# H1AR0.net
KiCad netlist of a schematic drawn in EAGLE
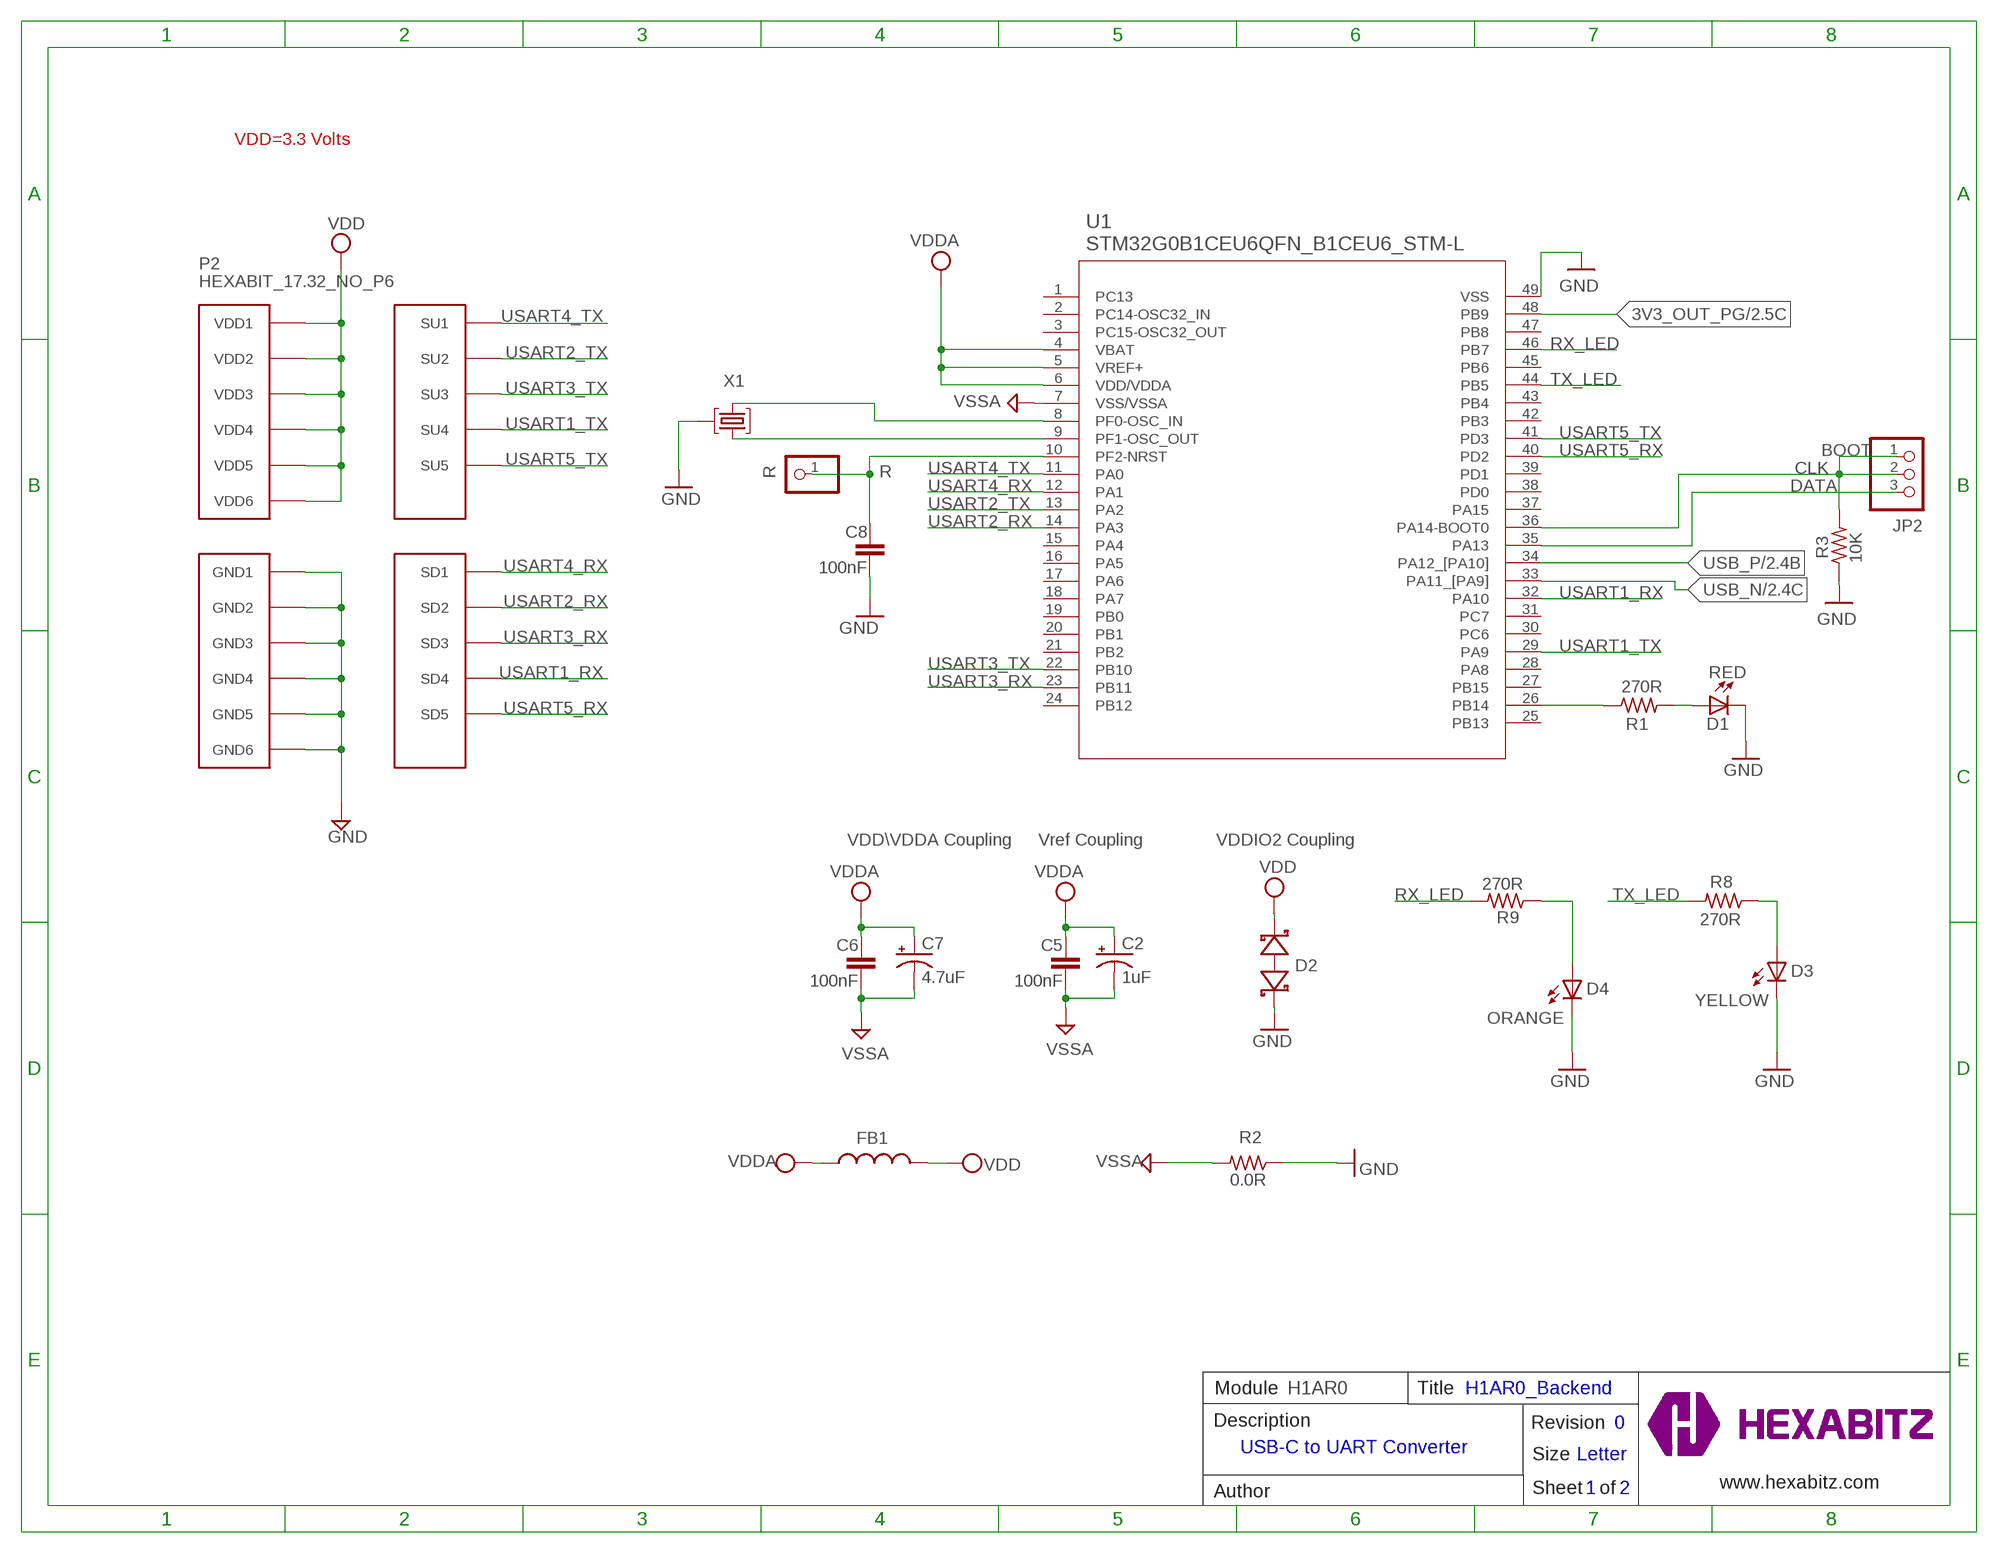
[diagram p0: schematic, sheet 1]
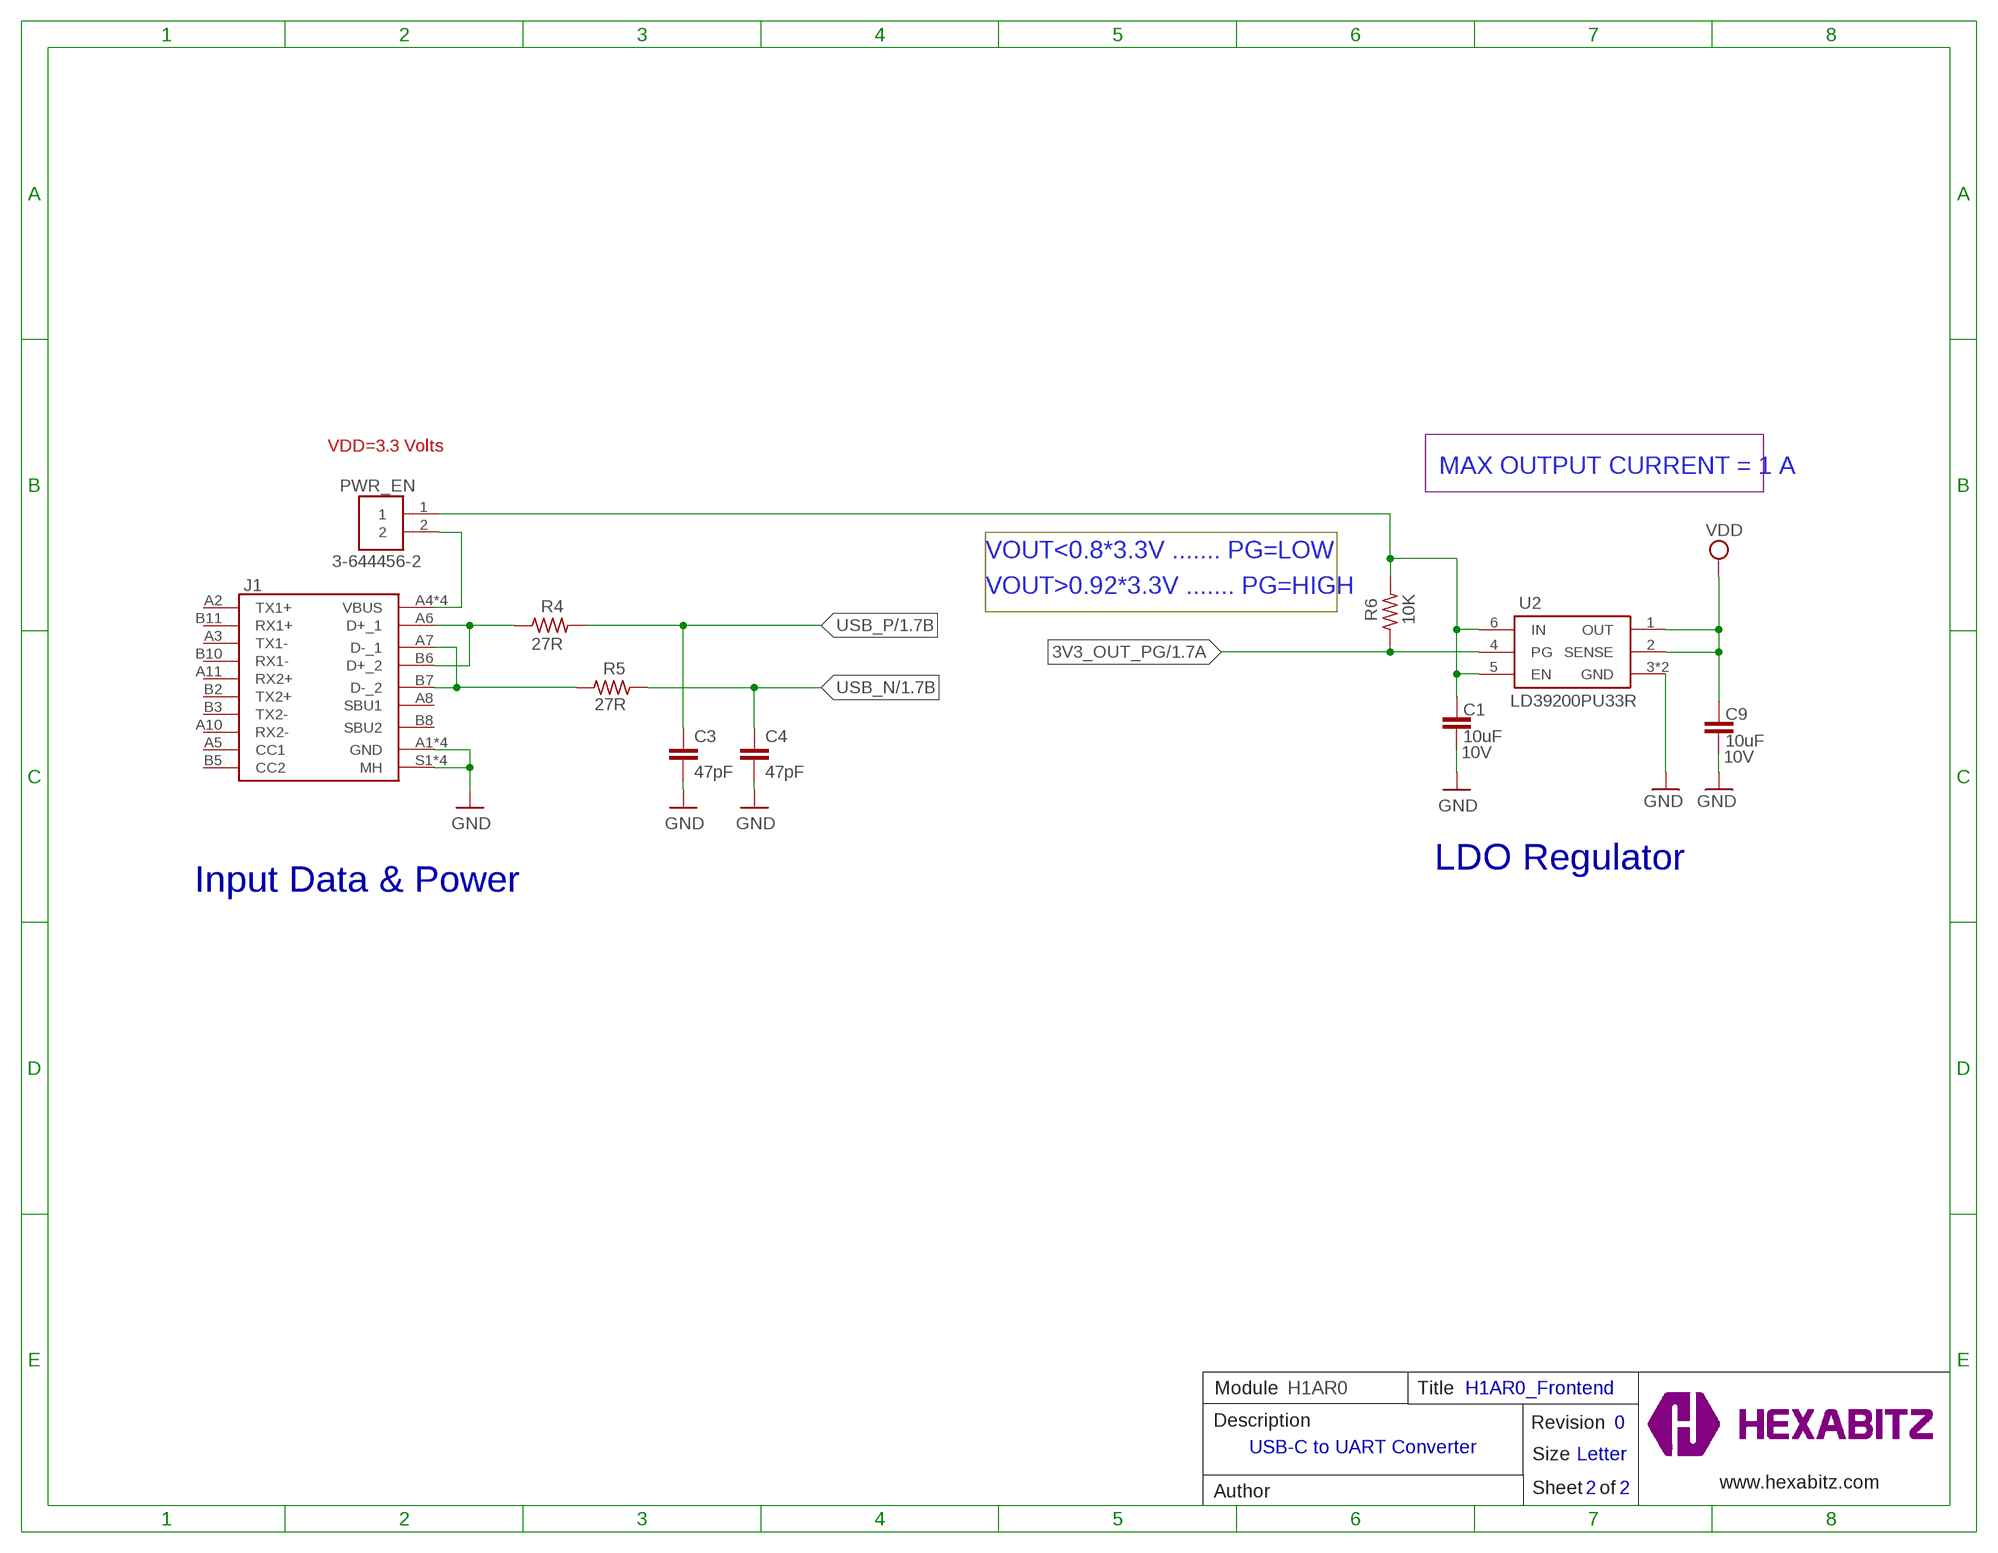
[diagram p1: schematic, sheet 2]

(export (version "E")
  (design (tool "Eeschema 10.0.6"))
  (components
    (comp (ref "C1")
      (value "10uF")
      (footprint "eagle-import:C-0805")
      (fields (field (name "MPN") "GRM187R61A226ME15") (field (name "VOLTAGE_RATING") "10V"))
      (libsource (lib "eagle-import") (part "C-0805"))
    )
    (comp (ref "C3")
      (value "47pF")
      (footprint "eagle-import:C-0603")
      (libsource (lib "eagle-import") (part "C-0603"))
    )
    (comp (ref "C4")
      (value "47pF")
      (footprint "eagle-import:C-0603")
      (libsource (lib "eagle-import") (part "C-0603"))
    )
    (comp (ref "C9")
      (value "10uF")
      (footprint "eagle-import:C-0805")
      (fields (field (name "MPN") "GRM187R61A226ME15") (field (name "VOLTAGE_RATING") "10V"))
      (libsource (lib "eagle-import") (part "C-0805"))
    )
    (comp (ref "J1")
      (value "12401610E4#2A12401610E42A")
      (footprint "eagle-import:AMPHENOL_12401610E4_2A")
      (libsource (lib "eagle-import") (part "12401610E4#2A12401610E42A"))
    )
    (comp (ref "PWR_EN")
      (value "3-644456-2")
      (footprint "eagle-import:TE_3-644456-2")
      (fields (field (name "MF") "TE Connectivity") (field (name "MPN") "87224-1"))
      (libsource (lib "eagle-import") (part "3-644456-2"))
    )
    (comp (ref "R4")
      (value "27R")
      (footprint "eagle-import:R-0603")
      (fields (field (name "TOLERANCE") "1%"))
      (libsource (lib "eagle-import") (part "R-0603"))
    )
    (comp (ref "R5")
      (value "27R")
      (footprint "eagle-import:R-0603")
      (fields (field (name "TOLERANCE") "1%"))
      (libsource (lib "eagle-import") (part "R-0603"))
    )
    (comp (ref "R6")
      (value "10K")
      (footprint "eagle-import:R-0603")
      (fields (field (name "TOLERANCE") "1%"))
      (libsource (lib "eagle-import") (part "R-0603"))
    )
    (comp (ref "U2")
      (value "LD39200PU33R")
      (footprint "eagle-import:SON95P300X300X100-7N")
      (fields (field (name "MOUSER_PART_NUMBER") "511-LD39200PU33R"))
      (libsource (lib "eagle-import") (part "LD39200PU33R"))
    )
    (comp (ref "C2")
      (value "1uF")
      (footprint "eagle-import:C-0805-POL")
      (libsource (lib "eagle-import") (part "C-0805-POL"))
    )
    (comp (ref "C5")
      (value "100nF")
      (footprint "eagle-import:C-0603")
      (libsource (lib "eagle-import") (part "C-0603"))
    )
    (comp (ref "C6")
      (value "100nF")
      (footprint "eagle-import:C-0603")
      (libsource (lib "eagle-import") (part "C-0603"))
    )
    (comp (ref "C7")
      (value "4.7uF")
      (footprint "eagle-import:C-0805-POL")
      (libsource (lib "eagle-import") (part "C-0805-POL"))
    )
    (comp (ref "C8")
      (value "100nF")
      (footprint "eagle-import:C-0603")
      (libsource (lib "eagle-import") (part "C-0603"))
    )
    (comp (ref "D1")
      (value "RED")
      (footprint "eagle-import:VLMS1300-GS08")
      (fields
        (field (name "MPN") "VLMS1300-GS08")
        (field (name "MFN") "Vishay")
        (field (name "MPN_1") "VLMS1300-GS08")
        (field (name "OCTOPART_URL") "https://octopart.com/vlms1300-gs08-vishay-21709201?r=sp&s=_gcP4_q8T1SC6PJQPTQ9yA")
      )
      (libsource (lib "eagle-import") (part "Hexabitz_VLMS1300-GS08"))
    )
    (comp (ref "D2")
      (value "BOURNS_CDSOD323-T03SCBOURNS_CDSOD323-T03SC_0_0")
      (footprint "eagle-import:BOURNS_CDSOD323-T03SC_0")
      (fields (field (name "MPN") "CDSOD323-T03SC"))
      (libsource (lib "eagle-import") (part "BOURNS_CDSOD323-T03SCBOURNS_CDSOD323-T03SC_0_0"))
    )
    (comp (ref "D3")
      (value "YELLOW")
      (footprint "eagle-import:VLMS1300-GS08")
      (fields
        (field (name "MPN") "VLMS1300-GS08")
        (field (name "OCTOPART_URL") "https://octopart.com/vlms1300-gs08-vishay-21709201?r=sp&s=_gcP4_q8T1SC6PJQPTQ9yA")
      )
      (libsource (lib "eagle-import") (part "VLMS1300-GS08"))
    )
    (comp (ref "D4")
      (value "ORANGE")
      (footprint "eagle-import:VLMS1300-GS08")
      (fields
        (field (name "MPN") "VLMS1300-GS08")
        (field (name "OCTOPART_URL") "https://octopart.com/vlms1300-gs08-vishay-21709201?r=sp&s=_gcP4_q8T1SC6PJQPTQ9yA")
      )
      (libsource (lib "eagle-import") (part "VLMS1300-GS08"))
    )
    (comp (ref "FB1")
      (value "FB-TDK_MMZ1608Y300B")
      (footprint "eagle-import:FB-TDK_MMZ1608Y300B")
      (fields
        (field (name "MFN") "TDK ")
        (field (name "MPN") "MMZ1608Y300B")
        (field (name "OCTOPART_URL") "https://octopart.com/mmz1608y300b-tdk-368280?r=sp&s=cd9_2ZEqQ9q9UNBuQgHAiA")
      )
      (libsource (lib "eagle-import") (part "FB-TDK_MMZ1608Y300B"))
    )
    (comp (ref "JP2")
      (value "PINHD-1X3")
      (footprint "eagle-import:1X03")
      (libsource (lib "eagle-import") (part "PINHD-1X3"))
    )
    (comp (ref "P2")
      (value "HEXABIT_17.32_NO_P6")
      (footprint "eagle-import:HEXABIT_17.32_NO_P6")
      (libsource (lib "eagle-import") (part "HEXABIT_?_NO_P617.32"))
    )
    (comp (ref "R")
      (value "R")
      (footprint "eagle-import:1X01")
      (fields (field (name "MPN") "87227-1"))
      (libsource (lib "eagle-import") (part "PINHD-1X1"))
    )
    (comp (ref "R1")
      (value "270R")
      (footprint "eagle-import:R-0603")
      (libsource (lib "eagle-import") (part "R-0603"))
    )
    (comp (ref "R2")
      (value "0.0R")
      (footprint "eagle-import:R-0603")
      (fields
        (field (name "MFN") "Yageo")
        (field (name "MPN") "RC0603JR-070RL")
        (field (name "OCTOPART_URL") "https://octopart.com/rc0603jr-070rl-yageo-1241539?r=sp&s=X2NteqRjRNWrnx42Y0aliA")
        (field (name "RESISTANCE") "0.0 Ohm")
      )
      (libsource (lib "eagle-import") (part "R-0603"))
    )
    (comp (ref "R3")
      (value "10K")
      (footprint "eagle-import:R-0603")
      (libsource (lib "eagle-import") (part "R-0603"))
    )
    (comp (ref "R8")
      (value "270R")
      (footprint "eagle-import:R-0603")
      (libsource (lib "eagle-import") (part "R-0603"))
    )
    (comp (ref "R9")
      (value "270R")
      (footprint "eagle-import:R-0603")
      (libsource (lib "eagle-import") (part "R-0603"))
    )
    (comp (ref "TRIMBLE-LOGO1")
      (value "HEXA-LOGO")
      (footprint "eagle-import:HEXA-LOGO")
      (libsource (lib "eagle-import") (part "HEXA-LOGO"))
    )
    (comp (ref "U1")
      (value "STM32G0B1CEU6QFN_B1CEU6_STM-L")
      (footprint "eagle-import:QFN_B1CEU6_STM-L")
      (fields
        (field (name "MANUFACTURER_PART_NUMBER") "STM32G0B1CEU6")
        (field (name "COPYRIGHT") "Copyright (C) 2021 Ultra Librarian. All rights reserved.")
      )
      (libsource (lib "eagle-import") (part "STM32G0B1CEU6QFN_B1CEU6_STM-L"))
    )
    (comp (ref "X1")
      (value "XTALL_CSTCE8M00G52")
      (footprint "eagle-import:XTALL_CSTCE8M00G52")
      (fields (field (name "MPN") "CSTCE8M00G52Z-R0"))
      (libsource (lib "eagle-import") (part "XTALL_CSTCE8M00G52"))
    )
  )
  (nets
    (net (code "1") (name "3V3_OUT_PG") (class "Default")
      (node (ref "R6") (pin "1") (pinfunction "1_1") (pintype "passive"))
      (node (ref "U1") (pin "48") (pinfunction "PB9_48") (pintype "bidirectional"))
      (node (ref "U2") (pin "4") (pinfunction "PG_4") (pintype "bidirectional"))
    )
    (net (code "2") (name "CLK") (class "Default")
      (node (ref "JP2") (pin "1") (pinfunction "1_1") (pintype "passive"))
      (node (ref "JP2") (pin "2") (pinfunction "2_2") (pintype "passive"))
      (node (ref "R3") (pin "2") (pinfunction "2_2") (pintype "passive"))
      (node (ref "U1") (pin "36") (pinfunction "PA14-BOOT0_36") (pintype "bidirectional"))
    )
    (net (code "3") (name "DATA") (class "Default")
      (node (ref "JP2") (pin "3") (pinfunction "3_3") (pintype "passive"))
      (node (ref "U1") (pin "35") (pinfunction "PA13_35") (pintype "bidirectional"))
    )
    (net (code "4") (name "GND") (class "Default")
      (node (ref "C1") (pin "1") (pinfunction "1_1") (pintype "passive"))
      (node (ref "C3") (pin "2") (pinfunction "2_2") (pintype "passive"))
      (node (ref "C4") (pin "2") (pinfunction "2_2") (pintype "passive"))
      (node (ref "C8") (pin "2") (pinfunction "2_2") (pintype "passive"))
      (node (ref "C9") (pin "1") (pinfunction "1_1") (pintype "passive"))
      (node (ref "D1") (pin "C") (pinfunction "C_C") (pintype "passive"))
      (node (ref "D2") (pin "1") (pinfunction "A_1") (pintype "passive"))
      (node (ref "D3") (pin "C") (pinfunction "C_C") (pintype "passive"))
      (node (ref "D4") (pin "C") (pinfunction "C_C") (pintype "passive"))
      (node (ref "J1") (pin "A1") (pinfunction "GND_A1") (pintype "bidirectional"))
      (node (ref "J1") (pin "A12") (pinfunction "GND_A12") (pintype "bidirectional"))
      (node (ref "J1") (pin "B1") (pinfunction "GND_B1") (pintype "bidirectional"))
      (node (ref "J1") (pin "B12") (pinfunction "GND_B12") (pintype "bidirectional"))
      (node (ref "J1") (pin "S1") (pinfunction "MH_S1") (pintype "bidirectional"))
      (node (ref "J1") (pin "S2") (pinfunction "MH_S2") (pintype "bidirectional"))
      (node (ref "J1") (pin "S3") (pinfunction "MH_S3") (pintype "bidirectional"))
      (node (ref "J1") (pin "S4") (pinfunction "MH_S4") (pintype "bidirectional"))
      (node (ref "P2") (pin "PAD_PD10") (pinfunction "GND4_PAD_PD10") (pintype "power_in"))
      (node (ref "P2") (pin "PAD_PD11") (pinfunction "GND5_PAD_PD11") (pintype "power_in"))
      (node (ref "P2") (pin "PAD_PD12") (pinfunction "GND6_PAD_PD12") (pintype "power_in"))
      (node (ref "P2") (pin "PAD_PD7") (pinfunction "GND1_PAD_PD7") (pintype "power_in"))
      (node (ref "P2") (pin "PAD_PD8") (pinfunction "GND2_PAD_PD8") (pintype "power_in"))
      (node (ref "P2") (pin "PAD_PD9") (pinfunction "GND3_PAD_PD9") (pintype "power_in"))
      (node (ref "R2") (pin "1") (pinfunction "1_1") (pintype "passive"))
      (node (ref "R3") (pin "1") (pinfunction "1_1") (pintype "passive"))
      (node (ref "U1") (pin "49") (pinfunction "VSS_49") (pintype "passive"))
      (node (ref "U2") (pin "3") (pinfunction "GND_3") (pintype "bidirectional"))
      (node (ref "U2") (pin "7") (pinfunction "GND_7") (pintype "bidirectional"))
      (node (ref "X1") (pin "P$2") (pinfunction "2_P$2") (pintype "passive"))
    )
    (net (code "5") (name "Net-(D1-PadA)") (class "Default")
      (node (ref "D1") (pin "A") (pinfunction "A_A") (pintype "passive"))
      (node (ref "R1") (pin "2") (pinfunction "2_2") (pintype "passive"))
    )
    (net (code "6") (name "Net-(D3-PadA)") (class "Default")
      (node (ref "D3") (pin "A") (pinfunction "A_A") (pintype "passive"))
      (node (ref "R8") (pin "1") (pinfunction "1_1") (pintype "passive"))
    )
    (net (code "7") (name "Net-(D4-PadA)") (class "Default")
      (node (ref "D4") (pin "A") (pinfunction "A_A") (pintype "passive"))
      (node (ref "R9") (pin "1") (pinfunction "1_1") (pintype "passive"))
    )
    (net (code "8") (name "Net-(J1-D+_1)") (class "Default")
      (node (ref "J1") (pin "A6") (pinfunction "D+_1_A6") (pintype "bidirectional"))
      (node (ref "J1") (pin "B6") (pinfunction "D+_2_B6") (pintype "bidirectional"))
      (node (ref "R4") (pin "1") (pinfunction "1_1") (pintype "passive"))
    )
    (net (code "9") (name "Net-(J1-D-_1)") (class "Default")
      (node (ref "J1") (pin "A7") (pinfunction "D-_1_A7") (pintype "bidirectional"))
      (node (ref "J1") (pin "B7") (pinfunction "D-_2_B7") (pintype "bidirectional"))
      (node (ref "R5") (pin "2") (pinfunction "2_2") (pintype "passive"))
    )
    (net (code "10") (name "Net-(J1-VBUS-PadA4)") (class "Default")
      (node (ref "J1") (pin "A4") (pinfunction "VBUS_A4") (pintype "bidirectional"))
      (node (ref "J1") (pin "A9") (pinfunction "VBUS_A9") (pintype "bidirectional"))
      (node (ref "J1") (pin "B4") (pinfunction "VBUS_B4") (pintype "bidirectional"))
      (node (ref "J1") (pin "B9") (pinfunction "VBUS_B9") (pintype "bidirectional"))
      (node (ref "PWR_EN") (pin "2") (pinfunction "2_2") (pintype "passive"))
    )
    (net (code "11") (name "Net-(U1-PB14)") (class "Default")
      (node (ref "R1") (pin "1") (pinfunction "1_1") (pintype "passive"))
      (node (ref "U1") (pin "26") (pinfunction "PB14_26") (pintype "bidirectional"))
    )
    (net (code "12") (name "Net-(U1-PF0-OSC_IN)") (class "Default")
      (node (ref "U1") (pin "8") (pinfunction "PF0-OSC_IN_8") (pintype "bidirectional"))
      (node (ref "X1") (pin "P$3") (pinfunction "3_P$3") (pintype "passive"))
    )
    (net (code "13") (name "Net-(U1-PF1-OSC_OUT)") (class "Default")
      (node (ref "U1") (pin "9") (pinfunction "PF1-OSC_OUT_9") (pintype "output"))
      (node (ref "X1") (pin "P$1") (pinfunction "1_P$1") (pintype "passive"))
    )
    (net (code "14") (name "Net-(U1-PF2-NRST)") (class "Default")
      (node (ref "C8") (pin "1") (pinfunction "1_1") (pintype "passive"))
      (node (ref "R") (pin "1") (pinfunction "1_1") (pintype "passive"))
      (node (ref "U1") (pin "10") (pinfunction "PF2-NRST_10") (pintype "bidirectional"))
    )
    (net (code "15") (name "Net-(U2-EN)") (class "Default")
      (node (ref "C1") (pin "2") (pinfunction "2_2") (pintype "passive"))
      (node (ref "PWR_EN") (pin "1") (pinfunction "1_1") (pintype "passive"))
      (node (ref "R6") (pin "2") (pinfunction "2_2") (pintype "passive"))
      (node (ref "U2") (pin "5") (pinfunction "EN_5") (pintype "bidirectional"))
      (node (ref "U2") (pin "6") (pinfunction "IN_6") (pintype "bidirectional"))
    )
    (net (code "16") (name "RX_LED") (class "Default")
      (node (ref "R9") (pin "2") (pinfunction "2_2") (pintype "passive"))
      (node (ref "U1") (pin "46") (pinfunction "PB7_46") (pintype "bidirectional"))
    )
    (net (code "17") (name "TX_LED") (class "Default")
      (node (ref "R8") (pin "2") (pinfunction "2_2") (pintype "passive"))
      (node (ref "U1") (pin "44") (pinfunction "PB5_44") (pintype "bidirectional"))
    )
    (net (code "18") (name "USART1_RX") (class "Default")
      (node (ref "P2") (pin "PAD_PD4") (pinfunction "SD4_PAD_PD4") (pintype "bidirectional"))
      (node (ref "U1") (pin "32") (pinfunction "PA10_32") (pintype "bidirectional"))
    )
    (net (code "19") (name "USART1_TX") (class "Default")
      (node (ref "P2") (pin "PAD_PU4") (pinfunction "SU4_PAD_PU4") (pintype "bidirectional"))
      (node (ref "U1") (pin "29") (pinfunction "PA9_29") (pintype "bidirectional"))
    )
    (net (code "20") (name "USART2_RX") (class "Default")
      (node (ref "P2") (pin "PAD_PD2") (pinfunction "SD2_PAD_PD2") (pintype "bidirectional"))
      (node (ref "U1") (pin "14") (pinfunction "PA3_14") (pintype "bidirectional"))
    )
    (net (code "21") (name "USART2_TX") (class "Default")
      (node (ref "P2") (pin "PAD_PU2") (pinfunction "SU2_PAD_PU2") (pintype "bidirectional"))
      (node (ref "U1") (pin "13") (pinfunction "PA2_13") (pintype "bidirectional"))
    )
    (net (code "22") (name "USART3_RX") (class "Default")
      (node (ref "P2") (pin "PAD_PD3") (pinfunction "SD3_PAD_PD3") (pintype "bidirectional"))
      (node (ref "U1") (pin "23") (pinfunction "PB11_23") (pintype "bidirectional"))
    )
    (net (code "23") (name "USART3_TX") (class "Default")
      (node (ref "P2") (pin "PAD_PU3") (pinfunction "SU3_PAD_PU3") (pintype "bidirectional"))
      (node (ref "U1") (pin "22") (pinfunction "PB10_22") (pintype "bidirectional"))
    )
    (net (code "24") (name "USART4_RX") (class "Default")
      (node (ref "P2") (pin "PAD_PD1") (pinfunction "SD1_PAD_PD1") (pintype "bidirectional"))
      (node (ref "U1") (pin "12") (pinfunction "PA1_12") (pintype "bidirectional"))
    )
    (net (code "25") (name "USART4_TX") (class "Default")
      (node (ref "P2") (pin "PAD_PU1") (pinfunction "SU1_PAD_PU1") (pintype "bidirectional"))
      (node (ref "U1") (pin "11") (pinfunction "PA0_11") (pintype "bidirectional"))
    )
    (net (code "26") (name "USART5_RX") (class "Default")
      (node (ref "P2") (pin "PAD_PD5") (pinfunction "SD5_PAD_PD5") (pintype "bidirectional"))
      (node (ref "U1") (pin "40") (pinfunction "PD2_40") (pintype "bidirectional"))
    )
    (net (code "27") (name "USART5_TX") (class "Default")
      (node (ref "P2") (pin "PAD_PU5") (pinfunction "SU5_PAD_PU5") (pintype "bidirectional"))
      (node (ref "U1") (pin "41") (pinfunction "PD3_41") (pintype "bidirectional"))
    )
    (net (code "28") (name "USB_N") (class "Default")
      (node (ref "C4") (pin "1") (pinfunction "1_1") (pintype "passive"))
      (node (ref "R5") (pin "1") (pinfunction "1_1") (pintype "passive"))
      (node (ref "U1") (pin "33") (pinfunction "PA11_[PA9]_33") (pintype "bidirectional"))
    )
    (net (code "29") (name "USB_P") (class "Default")
      (node (ref "C3") (pin "1") (pinfunction "1_1") (pintype "passive"))
      (node (ref "R4") (pin "2") (pinfunction "2_2") (pintype "passive"))
      (node (ref "U1") (pin "34") (pinfunction "PA12_[PA10]_34") (pintype "bidirectional"))
    )
    (net (code "30") (name "VDD") (class "Default")
      (node (ref "C9") (pin "2") (pinfunction "2_2") (pintype "passive"))
      (node (ref "D2") (pin "2") (pinfunction "C_2") (pintype "passive"))
      (node (ref "FB1") (pin "2") (pinfunction "2_2") (pintype "passive"))
      (node (ref "P2") (pin "PAD_PU10") (pinfunction "VDD4_PAD_PU10") (pintype "power_in"))
      (node (ref "P2") (pin "PAD_PU11") (pinfunction "VDD5_PAD_PU11") (pintype "power_in"))
      (node (ref "P2") (pin "PAD_PU12") (pinfunction "VDD6_PAD_PU12") (pintype "power_in"))
      (node (ref "P2") (pin "PAD_PU7") (pinfunction "VDD1_PAD_PU7") (pintype "power_in"))
      (node (ref "P2") (pin "PAD_PU8") (pinfunction "VDD2_PAD_PU8") (pintype "power_in"))
      (node (ref "P2") (pin "PAD_PU9") (pinfunction "VDD3_PAD_PU9") (pintype "power_in"))
      (node (ref "U2") (pin "1") (pinfunction "OUT_1") (pintype "bidirectional"))
      (node (ref "U2") (pin "2") (pinfunction "SENSE_2") (pintype "bidirectional"))
    )
    (net (code "31") (name "VDDA") (class "Default")
      (node (ref "C2") (pin "1") (pinfunction "+_1") (pintype "passive"))
      (node (ref "C5") (pin "1") (pinfunction "1_1") (pintype "passive"))
      (node (ref "C6") (pin "1") (pinfunction "1_1") (pintype "passive"))
      (node (ref "C7") (pin "1") (pinfunction "+_1") (pintype "passive"))
      (node (ref "FB1") (pin "1") (pinfunction "1_1") (pintype "passive"))
      (node (ref "U1") (pin "4") (pinfunction "VBAT_4") (pintype "passive"))
      (node (ref "U1") (pin "5") (pinfunction "VREF+_5") (pintype "power_in"))
      (node (ref "U1") (pin "6") (pinfunction "VDD/VDDA_6") (pintype "power_in"))
    )
    (net (code "32") (name "VSSA") (class "Default")
      (node (ref "C2") (pin "2") (pinfunction "-_2") (pintype "passive"))
      (node (ref "C5") (pin "2") (pinfunction "2_2") (pintype "passive"))
      (node (ref "C6") (pin "2") (pinfunction "2_2") (pintype "passive"))
      (node (ref "C7") (pin "2") (pinfunction "-_2") (pintype "passive"))
      (node (ref "R2") (pin "2") (pinfunction "2_2") (pintype "passive"))
      (node (ref "U1") (pin "7") (pinfunction "VSS/VSSA_7") (pintype "passive"))
    )
    (net (code "33") (name "unconnected-(J1-CC1-PadA5)") (class "Default")
      (node (ref "J1") (pin "A5") (pinfunction "CC1_A5") (pintype "bidirectional"))
    )
    (net (code "34") (name "unconnected-(J1-CC2-PadB5)") (class "Default")
      (node (ref "J1") (pin "B5") (pinfunction "CC2_B5") (pintype "bidirectional"))
    )
    (net (code "35") (name "unconnected-(J1-RX1+-PadB11)") (class "Default")
      (node (ref "J1") (pin "B11") (pinfunction "RX1+_B11") (pintype "bidirectional"))
    )
    (net (code "36") (name "unconnected-(J1-RX1--PadB10)") (class "Default")
      (node (ref "J1") (pin "B10") (pinfunction "RX1-_B10") (pintype "bidirectional"))
    )
    (net (code "37") (name "unconnected-(J1-RX2+-PadA11)") (class "Default")
      (node (ref "J1") (pin "A11") (pinfunction "RX2+_A11") (pintype "bidirectional"))
    )
    (net (code "38") (name "unconnected-(J1-RX2--PadA10)") (class "Default")
      (node (ref "J1") (pin "A10") (pinfunction "RX2-_A10") (pintype "bidirectional"))
    )
    (net (code "39") (name "unconnected-(J1-SBU1-PadA8)") (class "Default")
      (node (ref "J1") (pin "A8") (pinfunction "SBU1_A8") (pintype "bidirectional"))
    )
    (net (code "40") (name "unconnected-(J1-SBU2-PadB8)") (class "Default")
      (node (ref "J1") (pin "B8") (pinfunction "SBU2_B8") (pintype "bidirectional"))
    )
    (net (code "41") (name "unconnected-(J1-TX1+-PadA2)") (class "Default")
      (node (ref "J1") (pin "A2") (pinfunction "TX1+_A2") (pintype "bidirectional"))
    )
    (net (code "42") (name "unconnected-(J1-TX1--PadA3)") (class "Default")
      (node (ref "J1") (pin "A3") (pinfunction "TX1-_A3") (pintype "bidirectional"))
    )
    (net (code "43") (name "unconnected-(J1-TX2+-PadB2)") (class "Default")
      (node (ref "J1") (pin "B2") (pinfunction "TX2+_B2") (pintype "bidirectional"))
    )
    (net (code "44") (name "unconnected-(J1-TX2--PadB3)") (class "Default")
      (node (ref "J1") (pin "B3") (pinfunction "TX2-_B3") (pintype "bidirectional"))
    )
    (net (code "45") (name "unconnected-(U1-PA4-Pad15)") (class "Default")
      (node (ref "U1") (pin "15") (pinfunction "PA4_15") (pintype "bidirectional"))
    )
    (net (code "46") (name "unconnected-(U1-PA5-Pad16)") (class "Default")
      (node (ref "U1") (pin "16") (pinfunction "PA5_16") (pintype "bidirectional"))
    )
    (net (code "47") (name "unconnected-(U1-PA6-Pad17)") (class "Default")
      (node (ref "U1") (pin "17") (pinfunction "PA6_17") (pintype "bidirectional"))
    )
    (net (code "48") (name "unconnected-(U1-PA7-Pad18)") (class "Default")
      (node (ref "U1") (pin "18") (pinfunction "PA7_18") (pintype "bidirectional"))
    )
    (net (code "49") (name "unconnected-(U1-PA8-Pad28)") (class "Default")
      (node (ref "U1") (pin "28") (pinfunction "PA8_28") (pintype "bidirectional"))
    )
    (net (code "50") (name "unconnected-(U1-PA15-Pad37)") (class "Default")
      (node (ref "U1") (pin "37") (pinfunction "PA15_37") (pintype "bidirectional"))
    )
    (net (code "51") (name "unconnected-(U1-PB0-Pad19)") (class "Default")
      (node (ref "U1") (pin "19") (pinfunction "PB0_19") (pintype "bidirectional"))
    )
    (net (code "52") (name "unconnected-(U1-PB1-Pad20)") (class "Default")
      (node (ref "U1") (pin "20") (pinfunction "PB1_20") (pintype "bidirectional"))
    )
    (net (code "53") (name "unconnected-(U1-PB2-Pad21)") (class "Default")
      (node (ref "U1") (pin "21") (pinfunction "PB2_21") (pintype "bidirectional"))
    )
    (net (code "54") (name "unconnected-(U1-PB3-Pad42)") (class "Default")
      (node (ref "U1") (pin "42") (pinfunction "PB3_42") (pintype "bidirectional"))
    )
    (net (code "55") (name "unconnected-(U1-PB4-Pad43)") (class "Default")
      (node (ref "U1") (pin "43") (pinfunction "PB4_43") (pintype "bidirectional"))
    )
    (net (code "56") (name "unconnected-(U1-PB6-Pad45)") (class "Default")
      (node (ref "U1") (pin "45") (pinfunction "PB6_45") (pintype "bidirectional"))
    )
    (net (code "57") (name "unconnected-(U1-PB8-Pad47)") (class "Default")
      (node (ref "U1") (pin "47") (pinfunction "PB8_47") (pintype "bidirectional"))
    )
    (net (code "58") (name "unconnected-(U1-PB12-Pad24)") (class "Default")
      (node (ref "U1") (pin "24") (pinfunction "PB12_24") (pintype "bidirectional"))
    )
    (net (code "59") (name "unconnected-(U1-PB13-Pad25)") (class "Default")
      (node (ref "U1") (pin "25") (pinfunction "PB13_25") (pintype "bidirectional"))
    )
    (net (code "60") (name "unconnected-(U1-PB15-Pad27)") (class "Default")
      (node (ref "U1") (pin "27") (pinfunction "PB15_27") (pintype "bidirectional"))
    )
    (net (code "61") (name "unconnected-(U1-PC6-Pad30)") (class "Default")
      (node (ref "U1") (pin "30") (pinfunction "PC6_30") (pintype "bidirectional"))
    )
    (net (code "62") (name "unconnected-(U1-PC7-Pad31)") (class "Default")
      (node (ref "U1") (pin "31") (pinfunction "PC7_31") (pintype "bidirectional"))
    )
    (net (code "63") (name "unconnected-(U1-PC13-Pad1)") (class "Default")
      (node (ref "U1") (pin "1") (pinfunction "PC13_1") (pintype "bidirectional"))
    )
    (net (code "64") (name "unconnected-(U1-PC14-OSC32_IN-Pad2)") (class "Default")
      (node (ref "U1") (pin "2") (pinfunction "PC14-OSC32_IN_2") (pintype "bidirectional"))
    )
    (net (code "65") (name "unconnected-(U1-PC15-OSC32_OUT-Pad3)") (class "Default")
      (node (ref "U1") (pin "3") (pinfunction "PC15-OSC32_OUT_3") (pintype "output"))
    )
    (net (code "66") (name "unconnected-(U1-PD0-Pad38)") (class "Default")
      (node (ref "U1") (pin "38") (pinfunction "PD0_38") (pintype "bidirectional"))
    )
    (net (code "67") (name "unconnected-(U1-PD1-Pad39)") (class "Default")
      (node (ref "U1") (pin "39") (pinfunction "PD1_39") (pintype "bidirectional"))
    )
  )
)
